# USB-PHY.net
KiCad netlist of a schematic drawn in Altium Designer
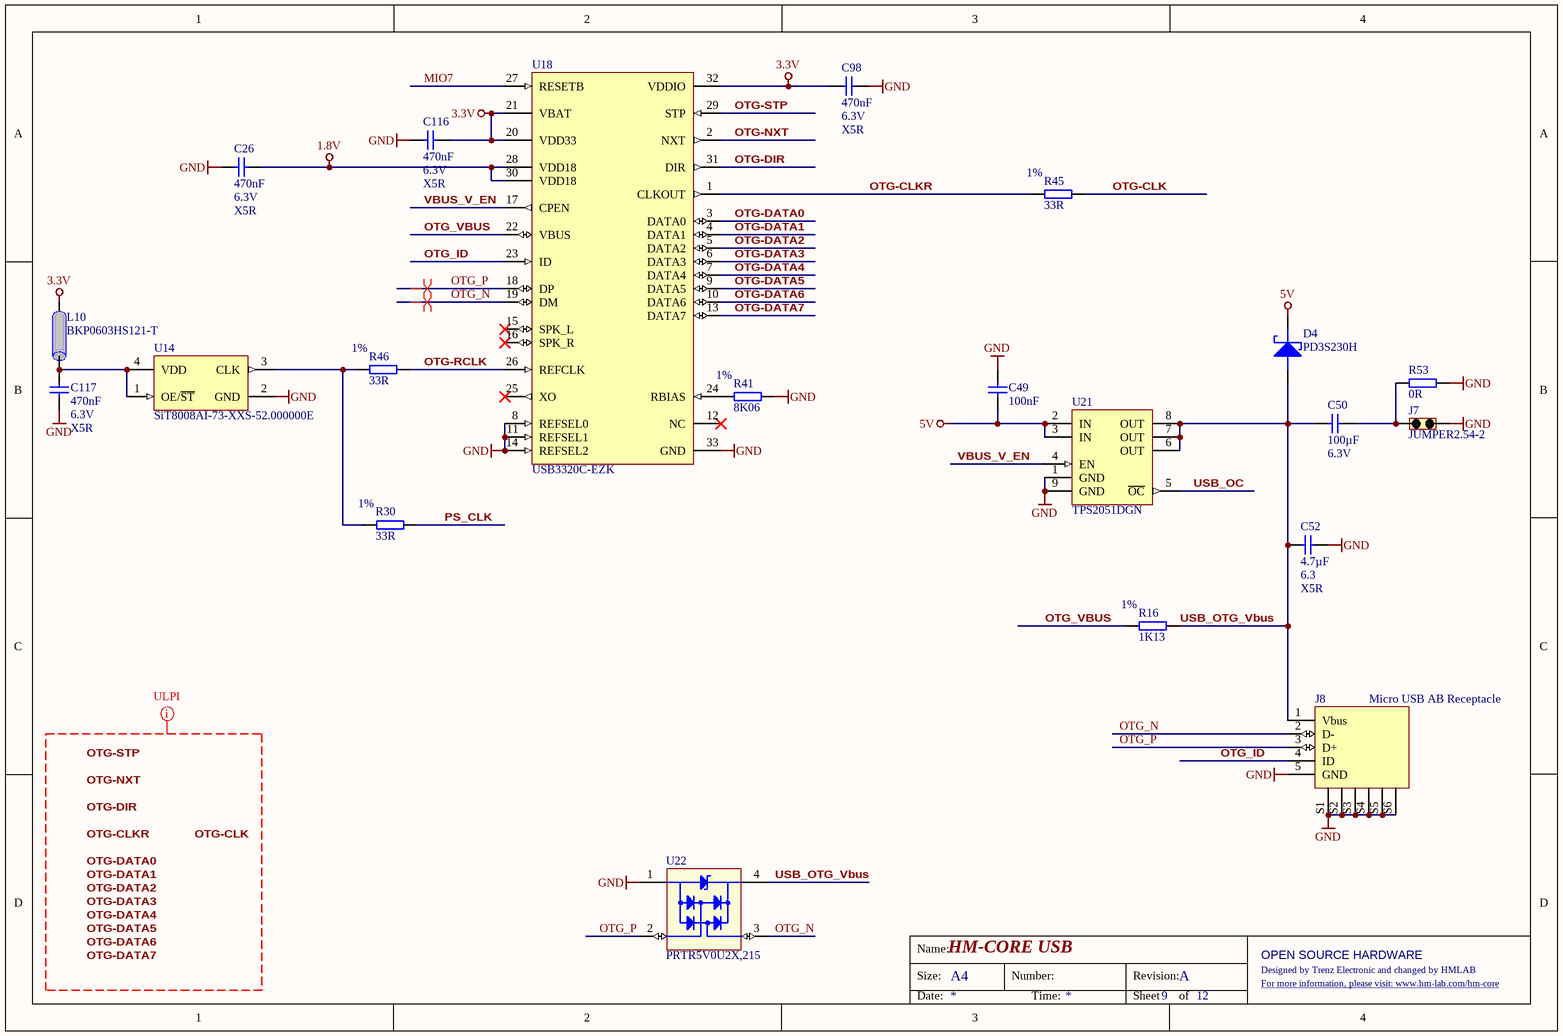
[diagram p0: USB-PHY.SchDoc]

(export (version "E")
  (design (tool "Eeschema 10.0.6"))
  (components
    (comp (ref "C26")
      (value "470nF")
      (footprint "CAPC0603X33N")
      (description "KON 470nF X5R 6.3V SMD 20%")
      (fields
        (field (name "VOLTAGE") "6.3V")
        (field (name "TECHNOLOGY") "X5R")
        (field (name "TOLERANCE") "20%")
      )
      (libsource (lib "TE") (part "CAP-NP"))
    )
    (comp (ref "C49")
      (value "100nF")
      (footprint "CAPC1005X55N")
      (description "KON 100nF 50V SMD AEC-Q200")
      (fields (field (name "VOLTAGE") "50V") (field (name "TOLERANCE") "10%"))
      (libsource (lib "TE") (part "CAP-NP"))
    )
    (comp (ref "C50")
      (value "100µF")
      (footprint "CAPC3216X180N")
      (description "KON 100µF 6,3V X5R SMD 20%")
      (fields (field (name "VOLTAGE") "6.3V") (field (name "TOLERANCE") "20%"))
      (libsource (lib "TE") (part "CAP-NP"))
    )
    (comp (ref "C52")
      (value "4.7µF")
      (footprint "CAPC1005X60N")
      (description "KON 4.7µF 6.3V X5R SMD 20%")
      (fields
        (field (name "VOLTAGE") "6.3")
        (field (name "TECHNOLOGY") "X5R")
        (field (name "TOLERANCE") "20%")
      )
      (libsource (lib "TE") (part "CAP-NP"))
    )
    (comp (ref "C98")
      (value "470nF")
      (footprint "CAPC0603X33N")
      (description "KON 470nF X5R 6.3V SMD 20%")
      (fields
        (field (name "VOLTAGE") "6.3V")
        (field (name "TECHNOLOGY") "X5R")
        (field (name "TOLERANCE") "20%")
      )
      (libsource (lib "TE") (part "CAP-NP"))
    )
    (comp (ref "C116")
      (value "470nF")
      (footprint "CAPC0603X33N")
      (description "KON 470nF X5R 6.3V SMD 20%")
      (fields
        (field (name "VOLTAGE") "6.3V")
        (field (name "TECHNOLOGY") "X5R")
        (field (name "TOLERANCE") "20%")
      )
      (libsource (lib "TE") (part "CAP-NP"))
    )
    (comp (ref "C117")
      (value "470nF")
      (footprint "CAPC0603X33N")
      (description "KON 470nF X5R 6.3V SMD 20%")
      (fields
        (field (name "VOLTAGE") "6.3V")
        (field (name "TECHNOLOGY") "X5R")
        (field (name "TOLERANCE") "20%")
      )
      (libsource (lib "TE") (part "CAP-NP"))
    )
    (comp (ref "D4") (value "PD3S230H") (footprint "PowerDI323") (libsource (lib "TE") (part "SCHOTTKY")))
    (comp (ref "J7")
      (value "JUMPER2.54-2")
      (footprint "JUMPER2_54-2")
      (description "Stiftleiste gerade 1-reihig, 2pol.")
      (libsource (lib "TE") (part "JUMPER2.54-2"))
    )
    (comp (ref "J8")
      (value "Micro USB AB Receptacle")
      (footprint "Micro USB ZX62-xx-5PA")
      (description "Micro USB AB Buchse")
      (libsource (lib "TE") (part "M USB SMD"))
    )
    (comp (ref "L10")
      (value "BKP0603HS121-T")
      (footprint "INDC0603X33N")
      (description "Ferritdurchführung SMD 0201")
      (fields (field (name "TOLERANCE") "25%"))
      (libsource (lib "TE") (part "Ferritperle"))
    )
    (comp (ref "R16")
      (value "1K13")
      (footprint "RESC1005X40N")
      (description "WID SMD 1K13 1% 0,063W")
      (fields (field (name "TOLERANCE") "1%"))
      (libsource (lib "TE") (part "RES"))
    )
    (comp (ref "R30")
      (value "33R")
      (footprint "RESC0603X26N")
      (description "WID SMD 33R 1% 0,05W")
      (fields (field (name "TOLERANCE") "1%"))
      (libsource (lib "TE") (part "RES"))
    )
    (comp (ref "R41")
      (value "8K06")
      (footprint "RESC1005X40N")
      (description "WID SMD 8K06 1% 0,063W")
      (fields (field (name "TOLERANCE") "1%"))
      (libsource (lib "TE") (part "RES"))
    )
    (comp (ref "R45")
      (value "33R")
      (footprint "RESC0603X26N")
      (description "WID SMD 33R 1% 0,05W")
      (fields (field (name "TOLERANCE") "1%"))
      (libsource (lib "TE") (part "RES"))
    )
    (comp (ref "R46")
      (value "33R")
      (footprint "RESC0603X26N")
      (description "WID SMD 33R 1% 0,05W")
      (fields (field (name "TOLERANCE") "1%"))
      (libsource (lib "TE") (part "RES"))
    )
    (comp (ref "R53")
      (value "0R")
      (footprint "RESC1005X40N")
      (description "WID SMD 0R 1% 0.063W AEC-Q200")
      (libsource (lib "TE") (part "RES"))
    )
    (comp (ref "U14")
      (value "SiT8008AI-73-XXS-52.000000E")
      (footprint "2016")
      (description "SiT8008AI-73-XXS-52.000000E MEMS Oszillator 52MHz")
      (libsource (lib "TE") (part "SiT8103"))
    )
    (comp (ref "U18")
      (value "USB3320C-EZK")
      (footprint "QFN50P500X500X100-33N-345")
      (libsource (lib "TE") (part "USB3320"))
    )
    (comp (ref "U21")
      (value "TPS2051DGN")
      (footprint "SOP65P488X107-9N-TI")
      (description "TPS2051BDGN")
      (libsource (lib "TE") (part "TPS2051DGN"))
    )
    (comp (ref "U22")
      (value "PRTR5V0U2X,215")
      (footprint "SOT190P229X114-4N")
      (libsource (lib "TE") (part "CD143A-SRxx"))
    )
  )
  (nets
    (net (code "1") (name "/MIO7") (class "Default")
      (node (ref "U18") (pin "27") (pinfunction "RESETB_27") (pintype "input"))
    )
    (net (code "2") (name "/OTG-CLK") (class "Default")
      (node (ref "R45") (pin "2") (pinfunction "2_2") (pintype "passive"))
    )
    (net (code "3") (name "/OTG-CLKR") (class "Default")
      (node (ref "R45") (pin "1") (pinfunction "1_1") (pintype "passive"))
      (node (ref "U18") (pin "1") (pinfunction "CLKOUT_1") (pintype "output"))
    )
    (net (code "4") (name "/OTG-DATA0") (class "Default")
      (node (ref "U18") (pin "3") (pinfunction "DATA0_3") (pintype "bidirectional"))
    )
    (net (code "5") (name "/OTG-DATA1") (class "Default")
      (node (ref "U18") (pin "4") (pinfunction "DATA1_4") (pintype "bidirectional"))
    )
    (net (code "6") (name "/OTG-DATA2") (class "Default")
      (node (ref "U18") (pin "5") (pinfunction "DATA2_5") (pintype "bidirectional"))
    )
    (net (code "7") (name "/OTG-DATA3") (class "Default")
      (node (ref "U18") (pin "6") (pinfunction "DATA3_6") (pintype "bidirectional"))
    )
    (net (code "8") (name "/OTG-DATA4") (class "Default")
      (node (ref "U18") (pin "7") (pinfunction "DATA4_7") (pintype "bidirectional"))
    )
    (net (code "9") (name "/OTG-DATA5") (class "Default")
      (node (ref "U18") (pin "9") (pinfunction "DATA5_9") (pintype "bidirectional"))
    )
    (net (code "10") (name "/OTG-DATA6") (class "Default")
      (node (ref "U18") (pin "10") (pinfunction "DATA6_10") (pintype "bidirectional"))
    )
    (net (code "11") (name "/OTG-DATA7") (class "Default")
      (node (ref "U18") (pin "13") (pinfunction "DATA7_13") (pintype "bidirectional"))
    )
    (net (code "12") (name "/OTG-DIR") (class "Default")
      (node (ref "U18") (pin "31") (pinfunction "DIR_31") (pintype "output"))
    )
    (net (code "13") (name "/OTG-NXT") (class "Default")
      (node (ref "U18") (pin "2") (pinfunction "NXT_2") (pintype "output"))
    )
    (net (code "14") (name "/OTG-RCLK") (class "Default")
      (node (ref "R46") (pin "2") (pinfunction "2_2") (pintype "passive"))
      (node (ref "U18") (pin "26") (pinfunction "REFCLK_26") (pintype "input"))
    )
    (net (code "15") (name "/OTG-STP") (class "Default")
      (node (ref "U18") (pin "29") (pinfunction "STP_29") (pintype "input"))
    )
    (net (code "16") (name "/OTG_ID") (class "Default")
      (node (ref "J8") (pin "4") (pinfunction "ID_4") (pintype "passive"))
      (node (ref "U18") (pin "23") (pinfunction "ID_23") (pintype "input"))
    )
    (net (code "17") (name "/OTG_N") (class "Default")
      (node (ref "J8") (pin "2") (pinfunction "D-_2") (pintype "bidirectional"))
      (node (ref "U18") (pin "19") (pinfunction "DM_19") (pintype "bidirectional"))
      (node (ref "U22") (pin "3") (pinfunction "I/O_3") (pintype "bidirectional"))
    )
    (net (code "18") (name "/OTG_P") (class "Default")
      (node (ref "J8") (pin "3") (pinfunction "D+_3") (pintype "bidirectional"))
      (node (ref "U18") (pin "18") (pinfunction "DP_18") (pintype "bidirectional"))
      (node (ref "U22") (pin "2") (pinfunction "I/O_2") (pintype "bidirectional"))
    )
    (net (code "19") (name "/OTG_VBUS") (class "Default")
      (node (ref "R16") (pin "1") (pinfunction "1_1") (pintype "passive"))
      (node (ref "U18") (pin "22") (pinfunction "VBUS_22") (pintype "bidirectional"))
    )
    (net (code "20") (name "/PS_CLK") (class "Default")
      (node (ref "R30") (pin "2") (pinfunction "2_2") (pintype "passive"))
    )
    (net (code "21") (name "/USB_OC") (class "Default")
      (node (ref "U21") (pin "5") (pinfunction "~{OC}_5") (pintype "output"))
    )
    (net (code "22") (name "/USB_OTG_Vbus") (class "Default")
      (node (ref "C50") (pin "2") (pinfunction "2_2") (pintype "passive"))
      (node (ref "C52") (pin "1") (pinfunction "1_1") (pintype "passive"))
      (node (ref "D4") (pin "2") (pinfunction "ANODE_2") (pintype "passive"))
      (node (ref "J8") (pin "1") (pinfunction "Vbus_1") (pintype "power_in"))
      (node (ref "R16") (pin "2") (pinfunction "2_2") (pintype "passive"))
      (node (ref "U21") (pin "6") (pinfunction "OUT_6") (pintype "power_in"))
      (node (ref "U21") (pin "7") (pinfunction "OUT_7") (pintype "power_in"))
      (node (ref "U21") (pin "8") (pinfunction "OUT_8") (pintype "power_in"))
      (node (ref "U22") (pin "4") (pinfunction "REF_4") (pintype "passive"))
    )
    (net (code "23") (name "/VBUS_V_EN") (class "Default")
      (node (ref "U18") (pin "17") (pinfunction "CPEN_17") (pintype "output"))
      (node (ref "U21") (pin "4") (pinfunction "EN_4") (pintype "input"))
    )
    (net (code "24") (name "1.8V") (class "Default")
      (node (ref "C26") (pin "1") (pinfunction "1_1") (pintype "passive"))
      (node (ref "U18") (pin "28") (pinfunction "VDD18_28") (pintype "power_in"))
      (node (ref "U18") (pin "30") (pinfunction "VDD18_30") (pintype "power_in"))
    )
    (net (code "25") (name "3.3V") (class "Default")
      (node (ref "C116") (pin "1") (pinfunction "1_1") (pintype "passive"))
      (node (ref "C98") (pin "2") (pinfunction "2_2") (pintype "passive"))
      (node (ref "L10") (pin "1") (pinfunction "1_1") (pintype "passive"))
      (node (ref "U18") (pin "20") (pinfunction "VDD33_20") (pintype "power_in"))
      (node (ref "U18") (pin "21") (pinfunction "VBAT_21") (pintype "power_in"))
      (node (ref "U18") (pin "32") (pinfunction "VDDIO_32") (pintype "power_in"))
    )
    (net (code "26") (name "5V") (class "Default")
      (node (ref "C49") (pin "2") (pinfunction "2_2") (pintype "passive"))
      (node (ref "D4") (pin "1") (pinfunction "KATHODE_1") (pintype "passive"))
      (node (ref "U21") (pin "2") (pinfunction "IN_2") (pintype "power_in"))
      (node (ref "U21") (pin "3") (pinfunction "IN_3") (pintype "power_in"))
    )
    (net (code "27") (name "GND") (class "Default")
      (node (ref "C116") (pin "2") (pinfunction "2_2") (pintype "passive"))
      (node (ref "C117") (pin "2") (pinfunction "2_2") (pintype "passive"))
      (node (ref "C26") (pin "2") (pinfunction "2_2") (pintype "passive"))
      (node (ref "C49") (pin "1") (pinfunction "1_1") (pintype "passive"))
      (node (ref "C52") (pin "2") (pinfunction "2_2") (pintype "passive"))
      (node (ref "C98") (pin "1") (pinfunction "1_1") (pintype "passive"))
      (node (ref "J7") (pin "2") (pinfunction "2_2") (pintype "passive"))
      (node (ref "J8") (pin "5") (pinfunction "GND_5") (pintype "power_in"))
      (node (ref "J8") (pin "S1") (pinfunction "S1_S1") (pintype "passive"))
      (node (ref "J8") (pin "S2") (pinfunction "S2_S2") (pintype "passive"))
      (node (ref "J8") (pin "S3") (pinfunction "S3_S3") (pintype "passive"))
      (node (ref "J8") (pin "S4") (pinfunction "S4_S4") (pintype "passive"))
      (node (ref "J8") (pin "S5") (pinfunction "S5_S5") (pintype "passive"))
      (node (ref "J8") (pin "S6") (pinfunction "S6_S6") (pintype "passive"))
      (node (ref "R41") (pin "2") (pinfunction "2_2") (pintype "passive"))
      (node (ref "R53") (pin "2") (pinfunction "2_2") (pintype "passive"))
      (node (ref "U14") (pin "2") (pinfunction "GND_2") (pintype "power_in"))
      (node (ref "U18") (pin "11") (pinfunction "REFSEL1_11") (pintype "input"))
      (node (ref "U18") (pin "14") (pinfunction "REFSEL2_14") (pintype "input"))
      (node (ref "U18") (pin "33") (pinfunction "GND_33") (pintype "power_in"))
      (node (ref "U18") (pin "8") (pinfunction "REFSEL0_8") (pintype "input"))
      (node (ref "U21") (pin "1") (pinfunction "GND_1") (pintype "power_in"))
      (node (ref "U21") (pin "9") (pinfunction "GND_9") (pintype "power_in"))
      (node (ref "U22") (pin "1") (pinfunction "GND_1") (pintype "passive"))
    )
    (net (code "28") (name "Net-(C50-Pad1)") (class "Default")
      (node (ref "C50") (pin "1") (pinfunction "1_1") (pintype "passive"))
      (node (ref "J7") (pin "1") (pinfunction "1_1") (pintype "passive"))
      (node (ref "R53") (pin "1") (pinfunction "1_1") (pintype "passive"))
    )
    (net (code "29") (name "Net-(U14-CLK)") (class "Default")
      (node (ref "R30") (pin "1") (pinfunction "1_1") (pintype "passive"))
      (node (ref "R46") (pin "1") (pinfunction "1_1") (pintype "passive"))
      (node (ref "U14") (pin "3") (pinfunction "CLK_3") (pintype "output"))
    )
    (net (code "30") (name "Net-(U14-OE{slash}~{ST})") (class "Default")
      (node (ref "C117") (pin "1") (pinfunction "1_1") (pintype "passive"))
      (node (ref "L10") (pin "2") (pinfunction "2_2") (pintype "passive"))
      (node (ref "U14") (pin "1") (pinfunction "OE/~{ST}_1") (pintype "input"))
      (node (ref "U14") (pin "4") (pinfunction "VDD_4") (pintype "power_in"))
    )
    (net (code "31") (name "Net-(U18-RBIAS)") (class "Default")
      (node (ref "R41") (pin "1") (pinfunction "1_1") (pintype "passive"))
      (node (ref "U18") (pin "24") (pinfunction "RBIAS_24") (pintype "input"))
    )
    (net (code "32") (name "unconnected-(U18-NC-Pad12)") (class "Default")
      (node (ref "U18") (pin "12") (pinfunction "NC_12") (pintype "passive+no_connect"))
    )
    (net (code "33") (name "unconnected-(U18-SPK_L-Pad15)") (class "Default")
      (node (ref "U18") (pin "15") (pinfunction "SPK_L_15") (pintype "bidirectional+no_connect"))
    )
    (net (code "34") (name "unconnected-(U18-SPK_R-Pad16)") (class "Default")
      (node (ref "U18") (pin "16") (pinfunction "SPK_R_16") (pintype "bidirectional+no_connect"))
    )
    (net (code "35") (name "unconnected-(U18-XO-Pad25)") (class "Default")
      (node (ref "U18") (pin "25") (pinfunction "XO_25") (pintype "output+no_connect"))
    )
  )
)
